# powerTestv1-0.net
KiCad netlist of a schematic drawn in EAGLE
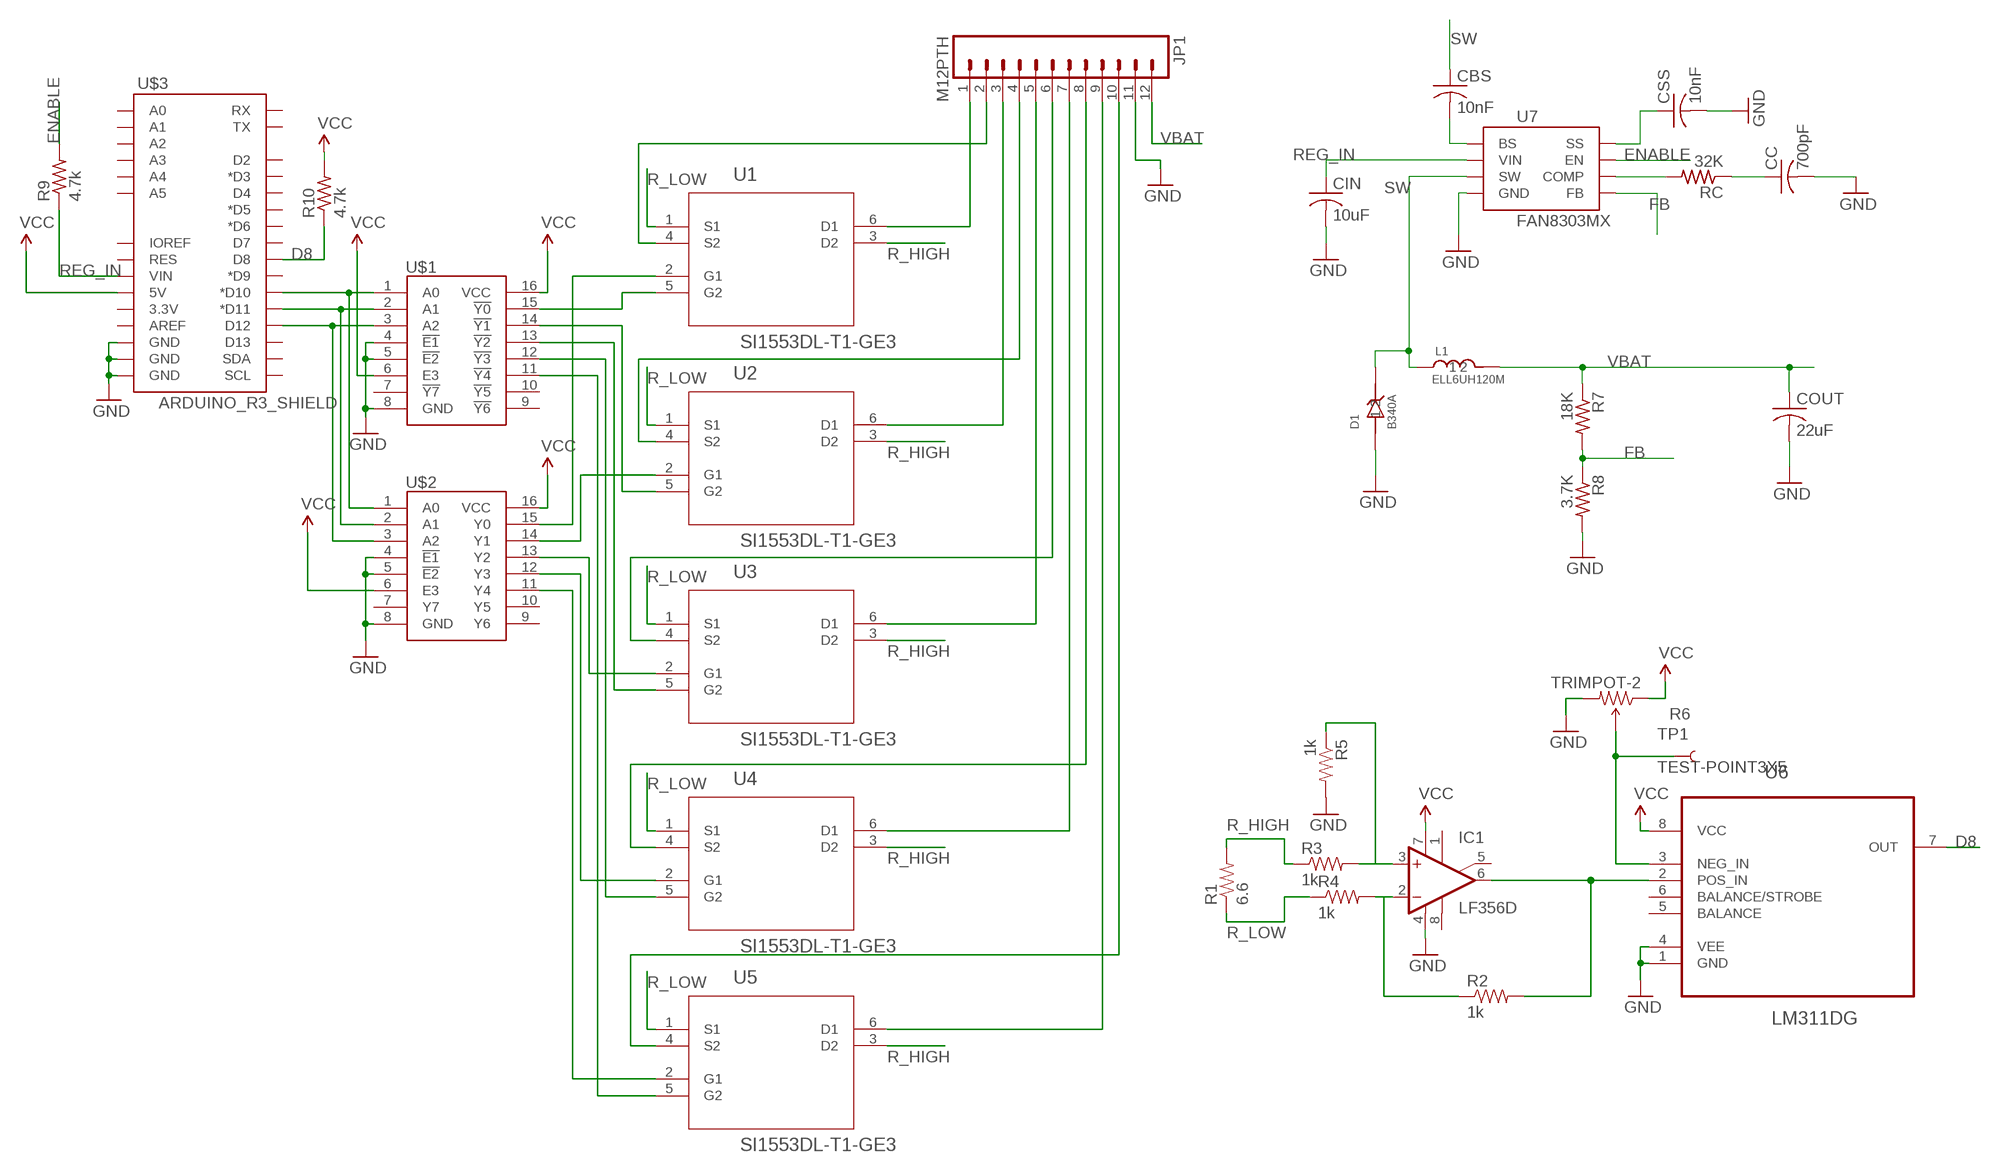
[diagram p0: schematic, sheet 1]

(export (version "E")
  (design (tool "Eeschema 10.0.6"))
  (components
    (comp (ref "CBS")
      (value "10nF")
      (footprint "eagle-import:C0603")
      (libsource (lib "eagle-import") (part "C-USC0603"))
    )
    (comp (ref "CC")
      (value "700pF")
      (footprint "eagle-import:C0603")
      (libsource (lib "eagle-import") (part "C-USC0603"))
    )
    (comp (ref "CIN")
      (value "10uF")
      (footprint "eagle-import:C0603")
      (libsource (lib "eagle-import") (part "C-USC0603"))
    )
    (comp (ref "COUT")
      (value "22uF")
      (footprint "eagle-import:C0603")
      (libsource (lib "eagle-import") (part "C-USC0603"))
    )
    (comp (ref "CSS")
      (value "10nF")
      (footprint "eagle-import:C0603")
      (libsource (lib "eagle-import") (part "C-USC0603"))
    )
    (comp (ref "D1")
      (value "B340A")
      (footprint "eagle-import:B340A")
      (libsource (lib "eagle-import") (part "B340A"))
    )
    (comp (ref "IC1")
      (value "LF356D")
      (footprint "eagle-import:SO08")
      (libsource (lib "eagle-import") (part "LF356D"))
    )
    (comp (ref "JP1")
      (value "M12PTH")
      (footprint "eagle-import:1X12")
      (libsource (lib "eagle-import") (part "M12PTH"))
    )
    (comp (ref "L1")
      (value "ELL6UH120M")
      (footprint "eagle-import:ELL6UH120M")
      (libsource (lib "eagle-import") (part "ELL6UH120M"))
    )
    (comp (ref "R1")
      (value "6.6")
      (footprint "eagle-import:AXIAL-0.8")
      (libsource (lib "eagle-import") (part "SparkFun-Resistors_RESISTORPTH-2W"))
    )
    (comp (ref "R2")
      (value "1k")
      (footprint "eagle-import:0603-RES")
      (libsource (lib "eagle-import") (part "RESISTOR0603-RES"))
    )
    (comp (ref "R3")
      (value "1k")
      (footprint "eagle-import:0603-RES")
      (libsource (lib "eagle-import") (part "RESISTOR0603-RES"))
    )
    (comp (ref "R4")
      (value "1k")
      (footprint "eagle-import:0603-RES")
      (libsource (lib "eagle-import") (part "RESISTOR0603-RES"))
    )
    (comp (ref "R5")
      (value "1k")
      (footprint "eagle-import:0603-RES")
      (libsource (lib "eagle-import") (part "RESISTOR0603-RES"))
    )
    (comp (ref "R6")
      (value "TRIMPOT-2")
      (footprint "eagle-import:TRIMPOT_TC33")
      (libsource (lib "eagle-import") (part "TRIMPOT-2"))
    )
    (comp (ref "R7")
      (value "18K")
      (footprint "eagle-import:R0603")
      (libsource (lib "eagle-import") (part "R-US_R0603"))
    )
    (comp (ref "R8")
      (value "3.7K")
      (footprint "eagle-import:R0603")
      (libsource (lib "eagle-import") (part "R-US_R0603"))
    )
    (comp (ref "R9")
      (value "4.7k")
      (footprint "eagle-import:R0603")
      (libsource (lib "eagle-import") (part "R-US_R0603"))
    )
    (comp (ref "R10")
      (value "4.7k")
      (footprint "eagle-import:R0603")
      (libsource (lib "eagle-import") (part "R-US_R0603"))
    )
    (comp (ref "RC")
      (value "32K")
      (footprint "eagle-import:R0603")
      (libsource (lib "eagle-import") (part "R-US_R0603"))
    )
    (comp (ref "TP1")
      (value "TEST-POINT3X5")
      (footprint "eagle-import:PAD.03X.05")
      (libsource (lib "eagle-import") (part "TEST-POINT3X5"))
    )
    (comp (ref "U$1")
      (value "74HC138SO16")
      (footprint "eagle-import:SO16")
      (libsource (lib "eagle-import") (part "74HC138SO16"))
    )
    (comp (ref "U$2")
      (value "74HC238SO16")
      (footprint "eagle-import:SO16")
      (libsource (lib "eagle-import") (part "74HC238SO16"))
    )
    (comp (ref "U$3")
      (value "ARDUINO_R3_SHIELD")
      (footprint "eagle-import:UNO_R3_SHIELD")
      (libsource (lib "eagle-import") (part "ARDUINO_R3_SHIELD"))
    )
    (comp (ref "U1")
      (value "SI1553DL-T1-GE3")
      (footprint "eagle-import:SOT65P210X110-6N")
      (libsource (lib "eagle-import") (part "SI1553DL-T1-GE3"))
    )
    (comp (ref "U2")
      (value "SI1553DL-T1-GE3")
      (footprint "eagle-import:SOT65P210X110-6N")
      (libsource (lib "eagle-import") (part "SI1553DL-T1-GE3"))
    )
    (comp (ref "U3")
      (value "SI1553DL-T1-GE3")
      (footprint "eagle-import:SOT65P210X110-6N")
      (libsource (lib "eagle-import") (part "SI1553DL-T1-GE3"))
    )
    (comp (ref "U4")
      (value "SI1553DL-T1-GE3")
      (footprint "eagle-import:SOT65P210X110-6N")
      (libsource (lib "eagle-import") (part "SI1553DL-T1-GE3"))
    )
    (comp (ref "U5")
      (value "SI1553DL-T1-GE3")
      (footprint "eagle-import:SOT65P210X110-6N")
      (libsource (lib "eagle-import") (part "SI1553DL-T1-GE3"))
    )
    (comp (ref "U6")
      (value "LM311DG")
      (footprint "eagle-import:SOIC127P600X175-8N")
      (libsource (lib "eagle-import") (part "LM311DG"))
    )
    (comp (ref "U7")
      (value "FAN8303MX")
      (footprint "eagle-import:FAN8303MX")
      (libsource (lib "eagle-import") (part "FAN8303MX"))
    )
  )
  (nets
    (net (code "1") (name "/D8") (class "Default")
      (node (ref "R10") (pin "1") (pinfunction "1_1") (pintype "passive"))
      (node (ref "U$3") (pin "D8") (pinfunction "D8_D8") (pintype "bidirectional"))
      (node (ref "U6") (pin "7") (pinfunction "OUT_7") (pintype "output"))
    )
    (net (code "2") (name "/ENABLE") (class "Default")
      (node (ref "R9") (pin "2") (pinfunction "2_2") (pintype "passive"))
      (node (ref "U7") (pin "P$7") (pinfunction "EN_P$7") (pintype "bidirectional"))
    )
    (net (code "3") (name "/FB") (class "Default")
      (node (ref "R7") (pin "2") (pinfunction "2_2") (pintype "passive"))
      (node (ref "R8") (pin "1") (pinfunction "1_1") (pintype "passive"))
      (node (ref "U7") (pin "P$5") (pinfunction "FB_P$5") (pintype "bidirectional"))
    )
    (net (code "4") (name "/REG_IN") (class "Default")
      (node (ref "CIN") (pin "1") (pinfunction "1_1") (pintype "passive"))
      (node (ref "R9") (pin "1") (pinfunction "1_1") (pintype "passive"))
      (node (ref "U$3") (pin "VIN") (pinfunction "VIN_VIN") (pintype "bidirectional"))
      (node (ref "U7") (pin "P$2") (pinfunction "VIN_P$2") (pintype "bidirectional"))
    )
    (net (code "5") (name "/R_HIGH") (class "Default")
      (node (ref "R1") (pin "P$2") (pinfunction "2_P$2") (pintype "passive"))
      (node (ref "R3") (pin "1") (pinfunction "1_1") (pintype "passive"))
      (node (ref "U1") (pin "3") (pinfunction "D2_3") (pintype "passive"))
      (node (ref "U2") (pin "3") (pinfunction "D2_3") (pintype "passive"))
      (node (ref "U3") (pin "3") (pinfunction "D2_3") (pintype "passive"))
      (node (ref "U4") (pin "3") (pinfunction "D2_3") (pintype "passive"))
      (node (ref "U5") (pin "3") (pinfunction "D2_3") (pintype "passive"))
    )
    (net (code "6") (name "/R_LOW") (class "Default")
      (node (ref "R1") (pin "P$1") (pinfunction "1_P$1") (pintype "passive"))
      (node (ref "R4") (pin "1") (pinfunction "1_1") (pintype "passive"))
      (node (ref "U1") (pin "1") (pinfunction "S1_1") (pintype "passive"))
      (node (ref "U2") (pin "1") (pinfunction "S1_1") (pintype "passive"))
      (node (ref "U3") (pin "1") (pinfunction "S1_1") (pintype "passive"))
      (node (ref "U4") (pin "1") (pinfunction "S1_1") (pintype "passive"))
      (node (ref "U5") (pin "1") (pinfunction "S1_1") (pintype "passive"))
    )
    (net (code "7") (name "/SW") (class "Default")
      (node (ref "CBS") (pin "1") (pinfunction "1_1") (pintype "passive"))
      (node (ref "D1") (pin "P$2") (pinfunction "2_P$2") (pintype "bidirectional"))
      (node (ref "L1") (pin "P$1") (pinfunction "1_P$1") (pintype "bidirectional"))
      (node (ref "U7") (pin "P$3") (pinfunction "SW_P$3") (pintype "bidirectional"))
    )
    (net (code "8") (name "/VBAT") (class "Default")
      (node (ref "COUT") (pin "1") (pinfunction "1_1") (pintype "passive"))
      (node (ref "JP1") (pin "12") (pinfunction "12_12") (pintype "passive"))
      (node (ref "L1") (pin "P$2") (pinfunction "2_P$2") (pintype "bidirectional"))
      (node (ref "R7") (pin "1") (pinfunction "1_1") (pintype "passive"))
    )
    (net (code "9") (name "GND") (class "Default")
      (node (ref "CC") (pin "2") (pinfunction "2_2") (pintype "passive"))
      (node (ref "CIN") (pin "2") (pinfunction "2_2") (pintype "passive"))
      (node (ref "COUT") (pin "2") (pinfunction "2_2") (pintype "passive"))
      (node (ref "CSS") (pin "2") (pinfunction "2_2") (pintype "passive"))
      (node (ref "D1") (pin "P$1") (pinfunction "1_P$1") (pintype "bidirectional"))
      (node (ref "IC1") (pin "4") (pinfunction "V-_4") (pintype "power_in"))
      (node (ref "JP1") (pin "11") (pinfunction "11_11") (pintype "passive"))
      (node (ref "R5") (pin "2") (pinfunction "2_2") (pintype "passive"))
      (node (ref "R6") (pin "3") (pinfunction "CW_3") (pintype "passive"))
      (node (ref "R8") (pin "2") (pinfunction "2_2") (pintype "passive"))
      (node (ref "U$1") (pin "4") (pinfunction "~{E1}_4") (pintype "input"))
      (node (ref "U$1") (pin "5") (pinfunction "~{E2}_5") (pintype "input"))
      (node (ref "U$1") (pin "8") (pinfunction "GND_8") (pintype "power_in"))
      (node (ref "U$2") (pin "4") (pinfunction "~{E1}_4") (pintype "input"))
      (node (ref "U$2") (pin "5") (pinfunction "~{E2}_5") (pintype "input"))
      (node (ref "U$2") (pin "8") (pinfunction "GND_8") (pintype "power_in"))
      (node (ref "U$3") (pin "GND@0") (pinfunction "GND_GND@0") (pintype "bidirectional"))
      (node (ref "U$3") (pin "GND@1") (pinfunction "GND_GND@1") (pintype "bidirectional"))
      (node (ref "U$3") (pin "GND@2") (pinfunction "GND_GND@2") (pintype "bidirectional"))
      (node (ref "U6") (pin "1") (pinfunction "GND_1") (pintype "passive"))
      (node (ref "U6") (pin "4") (pinfunction "VEE_4") (pintype "power_in"))
      (node (ref "U7") (pin "P$4") (pinfunction "GND_P$4") (pintype "bidirectional"))
    )
    (net (code "10") (name "Net-(CC-Pad1)") (class "Default")
      (node (ref "CC") (pin "1") (pinfunction "1_1") (pintype "passive"))
      (node (ref "RC") (pin "1") (pinfunction "1_1") (pintype "passive"))
    )
    (net (code "11") (name "Net-(IC1-+IN)") (class "Default")
      (node (ref "IC1") (pin "3") (pinfunction "+IN_3") (pintype "input"))
      (node (ref "R3") (pin "2") (pinfunction "2_2") (pintype "passive"))
      (node (ref "R5") (pin "1") (pinfunction "1_1") (pintype "passive"))
    )
    (net (code "12") (name "Net-(IC1--IN)") (class "Default")
      (node (ref "IC1") (pin "2") (pinfunction "-IN_2") (pintype "input"))
      (node (ref "R2") (pin "1") (pinfunction "1_1") (pintype "passive"))
      (node (ref "R4") (pin "2") (pinfunction "2_2") (pintype "passive"))
    )
    (net (code "13") (name "Net-(IC1-OUT)") (class "Default")
      (node (ref "IC1") (pin "6") (pinfunction "OUT_6") (pintype "output"))
      (node (ref "R2") (pin "2") (pinfunction "2_2") (pintype "passive"))
      (node (ref "U6") (pin "2") (pinfunction "POS_IN_2") (pintype "input"))
    )
    (net (code "14") (name "Net-(R6-WIPER)") (class "Default")
      (node (ref "R6") (pin "2") (pinfunction "WIPER_2") (pintype "passive"))
      (node (ref "TP1") (pin "P$1") (pinfunction "1_P$1") (pintype "bidirectional"))
      (node (ref "U6") (pin "3") (pinfunction "NEG_IN_3") (pintype "input"))
    )
    (net (code "15") (name "Net-(U$1-A0)") (class "Default")
      (node (ref "U$1") (pin "1") (pinfunction "A0_1") (pintype "input"))
      (node (ref "U$2") (pin "1") (pinfunction "A0_1") (pintype "input"))
      (node (ref "U$3") (pin "D10") (pinfunction "*D10_D10") (pintype "bidirectional"))
    )
    (net (code "16") (name "Net-(U$1-A1)") (class "Default")
      (node (ref "U$1") (pin "2") (pinfunction "A1_2") (pintype "input"))
      (node (ref "U$2") (pin "2") (pinfunction "A1_2") (pintype "input"))
      (node (ref "U$3") (pin "D11") (pinfunction "*D11_D11") (pintype "bidirectional"))
    )
    (net (code "17") (name "Net-(U$1-A2)") (class "Default")
      (node (ref "U$1") (pin "3") (pinfunction "A2_3") (pintype "input"))
      (node (ref "U$2") (pin "3") (pinfunction "A2_3") (pintype "input"))
      (node (ref "U$3") (pin "D12") (pinfunction "D12_D12") (pintype "bidirectional"))
    )
    (net (code "18") (name "Net-(U$1-~{Y0})") (class "Default")
      (node (ref "U$1") (pin "15") (pinfunction "~{Y0}_15") (pintype "output"))
      (node (ref "U1") (pin "5") (pinfunction "G2_5") (pintype "passive"))
    )
    (net (code "19") (name "Net-(U$1-~{Y1})") (class "Default")
      (node (ref "U$1") (pin "14") (pinfunction "~{Y1}_14") (pintype "output"))
      (node (ref "U2") (pin "5") (pinfunction "G2_5") (pintype "passive"))
    )
    (net (code "20") (name "Net-(U$1-~{Y2})") (class "Default")
      (node (ref "U$1") (pin "13") (pinfunction "~{Y2}_13") (pintype "output"))
      (node (ref "U3") (pin "5") (pinfunction "G2_5") (pintype "passive"))
    )
    (net (code "21") (name "Net-(U$1-~{Y3})") (class "Default")
      (node (ref "U$1") (pin "12") (pinfunction "~{Y3}_12") (pintype "output"))
      (node (ref "U4") (pin "5") (pinfunction "G2_5") (pintype "passive"))
    )
    (net (code "22") (name "Net-(U$1-~{Y4})") (class "Default")
      (node (ref "U$1") (pin "11") (pinfunction "~{Y4}_11") (pintype "output"))
      (node (ref "U5") (pin "5") (pinfunction "G2_5") (pintype "passive"))
    )
    (net (code "23") (name "Net-(U$2-Y0)") (class "Default")
      (node (ref "U$2") (pin "15") (pinfunction "Y0_15") (pintype "output"))
      (node (ref "U1") (pin "2") (pinfunction "G1_2") (pintype "passive"))
    )
    (net (code "24") (name "Net-(U$2-Y1)") (class "Default")
      (node (ref "U$2") (pin "14") (pinfunction "Y1_14") (pintype "output"))
      (node (ref "U2") (pin "2") (pinfunction "G1_2") (pintype "passive"))
    )
    (net (code "25") (name "Net-(U$2-Y2)") (class "Default")
      (node (ref "U$2") (pin "13") (pinfunction "Y2_13") (pintype "output"))
      (node (ref "U3") (pin "2") (pinfunction "G1_2") (pintype "passive"))
    )
    (net (code "26") (name "Net-(U$2-Y3)") (class "Default")
      (node (ref "U$2") (pin "12") (pinfunction "Y3_12") (pintype "output"))
      (node (ref "U4") (pin "2") (pinfunction "G1_2") (pintype "passive"))
    )
    (net (code "27") (name "Net-(U$2-Y4)") (class "Default")
      (node (ref "U$2") (pin "11") (pinfunction "Y4_11") (pintype "output"))
      (node (ref "U5") (pin "2") (pinfunction "G1_2") (pintype "passive"))
    )
    (net (code "28") (name "Net-(U1-D1)") (class "Default")
      (node (ref "JP1") (pin "1") (pinfunction "1_1") (pintype "passive"))
      (node (ref "U1") (pin "6") (pinfunction "D1_6") (pintype "passive"))
    )
    (net (code "29") (name "Net-(U1-S2)") (class "Default")
      (node (ref "JP1") (pin "2") (pinfunction "2_2") (pintype "passive"))
      (node (ref "U1") (pin "4") (pinfunction "S2_4") (pintype "passive"))
    )
    (net (code "30") (name "Net-(U2-D1)") (class "Default")
      (node (ref "JP1") (pin "3") (pinfunction "3_3") (pintype "passive"))
      (node (ref "U2") (pin "6") (pinfunction "D1_6") (pintype "passive"))
    )
    (net (code "31") (name "Net-(U2-S2)") (class "Default")
      (node (ref "JP1") (pin "4") (pinfunction "4_4") (pintype "passive"))
      (node (ref "U2") (pin "4") (pinfunction "S2_4") (pintype "passive"))
    )
    (net (code "32") (name "Net-(U3-D1)") (class "Default")
      (node (ref "JP1") (pin "5") (pinfunction "5_5") (pintype "passive"))
      (node (ref "U3") (pin "6") (pinfunction "D1_6") (pintype "passive"))
    )
    (net (code "33") (name "Net-(U3-S2)") (class "Default")
      (node (ref "JP1") (pin "6") (pinfunction "6_6") (pintype "passive"))
      (node (ref "U3") (pin "4") (pinfunction "S2_4") (pintype "passive"))
    )
    (net (code "34") (name "Net-(U4-D1)") (class "Default")
      (node (ref "JP1") (pin "7") (pinfunction "7_7") (pintype "passive"))
      (node (ref "U4") (pin "6") (pinfunction "D1_6") (pintype "passive"))
    )
    (net (code "35") (name "Net-(U4-S2)") (class "Default")
      (node (ref "JP1") (pin "8") (pinfunction "8_8") (pintype "passive"))
      (node (ref "U4") (pin "4") (pinfunction "S2_4") (pintype "passive"))
    )
    (net (code "36") (name "Net-(U5-D1)") (class "Default")
      (node (ref "JP1") (pin "9") (pinfunction "9_9") (pintype "passive"))
      (node (ref "U5") (pin "6") (pinfunction "D1_6") (pintype "passive"))
    )
    (net (code "37") (name "Net-(U5-S2)") (class "Default")
      (node (ref "JP1") (pin "10") (pinfunction "10_10") (pintype "passive"))
      (node (ref "U5") (pin "4") (pinfunction "S2_4") (pintype "passive"))
    )
    (net (code "38") (name "Net-(U7-BS)") (class "Default")
      (node (ref "CBS") (pin "2") (pinfunction "2_2") (pintype "passive"))
      (node (ref "U7") (pin "P$1") (pinfunction "BS_P$1") (pintype "bidirectional"))
    )
    (net (code "39") (name "Net-(U7-COMP)") (class "Default")
      (node (ref "RC") (pin "2") (pinfunction "2_2") (pintype "passive"))
      (node (ref "U7") (pin "P$6") (pinfunction "COMP_P$6") (pintype "bidirectional"))
    )
    (net (code "40") (name "Net-(U7-SS)") (class "Default")
      (node (ref "CSS") (pin "1") (pinfunction "1_1") (pintype "passive"))
      (node (ref "U7") (pin "P$8") (pinfunction "SS_P$8") (pintype "bidirectional"))
    )
    (net (code "41") (name "VCC") (class "Default")
      (node (ref "IC1") (pin "7") (pinfunction "V+_7") (pintype "power_in"))
      (node (ref "R10") (pin "2") (pinfunction "2_2") (pintype "passive"))
      (node (ref "R6") (pin "1") (pinfunction "CCW_1") (pintype "passive"))
      (node (ref "U$1") (pin "16") (pinfunction "VCC_16") (pintype "power_in"))
      (node (ref "U$1") (pin "6") (pinfunction "E3_6") (pintype "input"))
      (node (ref "U$2") (pin "16") (pinfunction "VCC_16") (pintype "power_in"))
      (node (ref "U$2") (pin "6") (pinfunction "E3_6") (pintype "input"))
      (node (ref "U$3") (pin "5V") (pinfunction "5V_5V") (pintype "bidirectional"))
      (node (ref "U6") (pin "8") (pinfunction "VCC_8") (pintype "power_in"))
    )
    (net (code "42") (name "unconnected-(IC1-ON1-Pad1)") (class "Default")
      (node (ref "IC1") (pin "1") (pinfunction "ON1_1") (pintype "passive"))
    )
    (net (code "43") (name "unconnected-(IC1-ON2-Pad5)") (class "Default")
      (node (ref "IC1") (pin "5") (pinfunction "ON2_5") (pintype "passive"))
    )
    (net (code "44") (name "unconnected-(IC1-OPT-Pad8)") (class "Default")
      (node (ref "IC1") (pin "8") (pinfunction "OPT_8") (pintype "passive"))
    )
    (net (code "45") (name "unconnected-(U$1-~{Y5}-Pad10)") (class "Default")
      (node (ref "U$1") (pin "10") (pinfunction "~{Y5}_10") (pintype "output"))
    )
    (net (code "46") (name "unconnected-(U$1-~{Y6}-Pad9)") (class "Default")
      (node (ref "U$1") (pin "9") (pinfunction "~{Y6}_9") (pintype "output"))
    )
    (net (code "47") (name "unconnected-(U$1-~{Y7}-Pad7)") (class "Default")
      (node (ref "U$1") (pin "7") (pinfunction "~{Y7}_7") (pintype "output"))
    )
    (net (code "48") (name "unconnected-(U$2-Y5-Pad10)") (class "Default")
      (node (ref "U$2") (pin "10") (pinfunction "Y5_10") (pintype "output"))
    )
    (net (code "49") (name "unconnected-(U$2-Y6-Pad9)") (class "Default")
      (node (ref "U$2") (pin "9") (pinfunction "Y6_9") (pintype "output"))
    )
    (net (code "50") (name "unconnected-(U$2-Y7-Pad7)") (class "Default")
      (node (ref "U$2") (pin "7") (pinfunction "Y7_7") (pintype "output"))
    )
    (net (code "51") (name "unconnected-(U$3-*D3-PadD3)") (class "Default")
      (node (ref "U$3") (pin "D3") (pinfunction "*D3_D3") (pintype "bidirectional"))
    )
    (net (code "52") (name "unconnected-(U$3-*D5-PadD5)") (class "Default")
      (node (ref "U$3") (pin "D5") (pinfunction "*D5_D5") (pintype "bidirectional"))
    )
    (net (code "53") (name "unconnected-(U$3-*D6-PadD6)") (class "Default")
      (node (ref "U$3") (pin "D6") (pinfunction "*D6_D6") (pintype "bidirectional"))
    )
    (net (code "54") (name "unconnected-(U$3-*D9-PadD9)") (class "Default")
      (node (ref "U$3") (pin "D9") (pinfunction "*D9_D9") (pintype "bidirectional"))
    )
    (net (code "55") (name "unconnected-(U$3-Pad3.3V)") (class "Default")
      (node (ref "U$3") (pin "3.3V") (pinfunction "3.3V_3.3V") (pintype "bidirectional"))
    )
    (net (code "56") (name "unconnected-(U$3-PadA0)") (class "Default")
      (node (ref "U$3") (pin "A0") (pinfunction "A0_A0") (pintype "bidirectional"))
    )
    (net (code "57") (name "unconnected-(U$3-PadA1)") (class "Default")
      (node (ref "U$3") (pin "A1") (pinfunction "A1_A1") (pintype "bidirectional"))
    )
    (net (code "58") (name "unconnected-(U$3-PadA2)") (class "Default")
      (node (ref "U$3") (pin "A2") (pinfunction "A2_A2") (pintype "bidirectional"))
    )
    (net (code "59") (name "unconnected-(U$3-PadA3)") (class "Default")
      (node (ref "U$3") (pin "A3") (pinfunction "A3_A3") (pintype "bidirectional"))
    )
    (net (code "60") (name "unconnected-(U$3-PadA4)") (class "Default")
      (node (ref "U$3") (pin "A4") (pinfunction "A4_A4") (pintype "bidirectional"))
    )
    (net (code "61") (name "unconnected-(U$3-PadA5)") (class "Default")
      (node (ref "U$3") (pin "A5") (pinfunction "A5_A5") (pintype "bidirectional"))
    )
    (net (code "62") (name "unconnected-(U$3-PadAREF)") (class "Default")
      (node (ref "U$3") (pin "AREF") (pinfunction "AREF_AREF") (pintype "bidirectional"))
    )
    (net (code "63") (name "unconnected-(U$3-PadD2)") (class "Default")
      (node (ref "U$3") (pin "D2") (pinfunction "D2_D2") (pintype "bidirectional"))
    )
    (net (code "64") (name "unconnected-(U$3-PadD4)") (class "Default")
      (node (ref "U$3") (pin "D4") (pinfunction "D4_D4") (pintype "bidirectional"))
    )
    (net (code "65") (name "unconnected-(U$3-PadD7)") (class "Default")
      (node (ref "U$3") (pin "D7") (pinfunction "D7_D7") (pintype "bidirectional"))
    )
    (net (code "66") (name "unconnected-(U$3-PadD13)") (class "Default")
      (node (ref "U$3") (pin "D13") (pinfunction "D13_D13") (pintype "bidirectional"))
    )
    (net (code "67") (name "unconnected-(U$3-PadIOREF)") (class "Default")
      (node (ref "U$3") (pin "IOREF") (pinfunction "IOREF_IOREF") (pintype "bidirectional"))
    )
    (net (code "68") (name "unconnected-(U$3-PadRES)") (class "Default")
      (node (ref "U$3") (pin "RES") (pinfunction "RES_RES") (pintype "bidirectional"))
    )
    (net (code "69") (name "unconnected-(U$3-PadRX)") (class "Default")
      (node (ref "U$3") (pin "RX") (pinfunction "RX_RX") (pintype "bidirectional"))
    )
    (net (code "70") (name "unconnected-(U$3-PadSCL)") (class "Default")
      (node (ref "U$3") (pin "SCL") (pinfunction "SCL_SCL") (pintype "bidirectional"))
    )
    (net (code "71") (name "unconnected-(U$3-PadSDA)") (class "Default")
      (node (ref "U$3") (pin "SDA") (pinfunction "SDA_SDA") (pintype "bidirectional"))
    )
    (net (code "72") (name "unconnected-(U$3-PadTX)") (class "Default")
      (node (ref "U$3") (pin "TX") (pinfunction "TX_TX") (pintype "bidirectional"))
    )
    (net (code "73") (name "unconnected-(U6-BALANCE-Pad5)") (class "Default")
      (node (ref "U6") (pin "5") (pinfunction "BALANCE_5") (pintype "input"))
    )
    (net (code "74") (name "unconnected-(U6-BALANCE{slash}STROBE-Pad6)") (class "Default")
      (node (ref "U6") (pin "6") (pinfunction "BALANCE/STROBE_6") (pintype "input"))
    )
  )
)
